# dronev2.net
KiCad netlist of a schematic drawn in Altium Designer
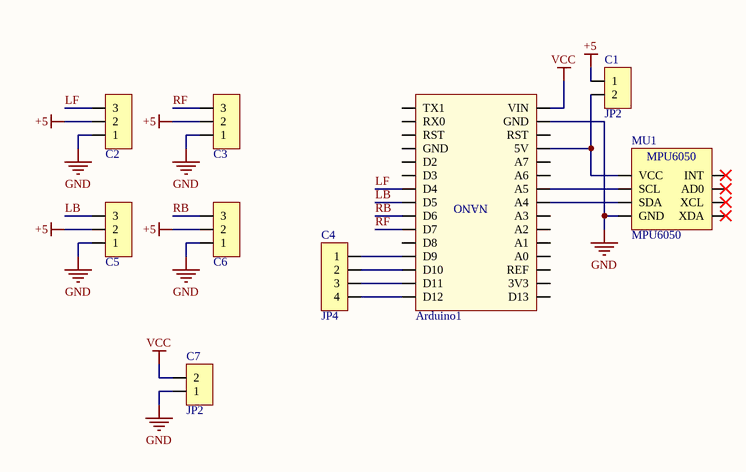
[diagram p0: dronev2.SchDoc]

(export (version "E")
  (design (tool "Eeschema 10.0.6"))
  (components
    (comp (ref "Arduino1")
      (value "Arduino Nano")
      (footprint "Arduino Nano")
      (description "Arduino NANO")
      (libsource (lib "LIBRARY") (part "Arduino Nano"))
    )
    (comp (ref "C1")
      (value "JP2")
      (footprint "JP2-CLOSED")
      (description "WR-PHD 2.54 mm Angled Socket Header")
      (fields
        (field (name "MANUFACTURER") "Würth Elektronik eiSos GmbH")
        (field (name "PARTNO") "613002143121")
        (field (name "CREATED BY") "Karrer Zheng")
      )
      (libsource (lib "") (part "JP2_1"))
    )
    (comp (ref "C2")
      (value "JP3")
      (footprint "JP3-C1T")
      (description "WR-PHD 2.54 mm Angled Socket Header")
      (fields
        (field (name "MANUFACTURER") "Würth Elektronik eiSos GmbH")
        (field (name "PARTNO") "613003143121")
        (field (name "CREATED BY") "Karrer Zheng")
      )
      (libsource (lib "LIBRARY") (part "JP3"))
    )
    (comp (ref "C3")
      (value "JP3")
      (footprint "JP3-C1T")
      (description "WR-PHD 2.54 mm Angled Socket Header")
      (fields
        (field (name "MANUFACTURER") "Würth Elektronik eiSos GmbH")
        (field (name "PARTNO") "613003143121")
        (field (name "CREATED BY") "Karrer Zheng")
      )
      (libsource (lib "LIBRARY") (part "JP3"))
    )
    (comp (ref "C4")
      (value "JP4")
      (footprint "JP4-C1T")
      (description "WR-PHD 2.54 mm Angled Socket Header")
      (fields
        (field (name "MANUFACTURER") "Würth Elektronik eiSos GmbH")
        (field (name "PARTNO") "613004143121")
        (field (name "CREATED BY") "Karrer Zheng")
      )
      (libsource (lib "LIBRARY") (part "JP4"))
    )
    (comp (ref "C5")
      (value "JP3")
      (footprint "JP3-C1T")
      (description "WR-PHD 2.54 mm Angled Socket Header")
      (fields
        (field (name "MANUFACTURER") "Würth Elektronik eiSos GmbH")
        (field (name "PARTNO") "613003143121")
        (field (name "CREATED BY") "Karrer Zheng")
      )
      (libsource (lib "LIBRARY") (part "JP3"))
    )
    (comp (ref "C6")
      (value "JP3")
      (footprint "JP3-C1T")
      (description "WR-PHD 2.54 mm Angled Socket Header")
      (fields
        (field (name "MANUFACTURER") "Würth Elektronik eiSos GmbH")
        (field (name "PARTNO") "613003143121")
        (field (name "CREATED BY") "Karrer Zheng")
      )
      (libsource (lib "LIBRARY") (part "JP3"))
    )
    (comp (ref "C7")
      (value "JP2")
      (footprint "JP2-C1T")
      (description "WR-PHD 2.54 mm Angled Socket Header")
      (fields
        (field (name "MANUFACTURER") "Würth Elektronik eiSos GmbH")
        (field (name "PARTNO") "613002143121")
        (field (name "CREATED BY") "Karrer Zheng")
      )
      (libsource (lib "LIBRARY") (part "JP2"))
    )
    (comp (ref "MU1")
      (value "MPU6050")
      (footprint "MPU6050")
      (fields
        (field (name "MANUFACTURER") "Würth Elektronik eiSos GmbH")
        (field (name "PARTNO") "613004143121")
        (field (name "CREATED BY") "Karrer Zheng")
      )
      (libsource (lib "LIBRARY") (part "MPU6050"))
    )
  )
  (nets
    (net (code "1") (name "+5") (class "Default")
      (node (ref "C1") (pin "1") (pinfunction "1_1") (pintype "passive"))
      (node (ref "C2") (pin "2") (pinfunction "2_2") (pintype "passive"))
      (node (ref "C3") (pin "2") (pinfunction "2_2") (pintype "passive"))
      (node (ref "C5") (pin "2") (pinfunction "2_2") (pintype "passive"))
      (node (ref "C6") (pin "2") (pinfunction "2_2") (pintype "passive"))
    )
    (net (code "2") (name "/LB") (class "Default")
      (node (ref "Arduino1") (pin "D5") (pinfunction "D5_D5") (pintype "passive"))
      (node (ref "C5") (pin "3") (pinfunction "3_3") (pintype "passive"))
    )
    (net (code "3") (name "/LF") (class "Default")
      (node (ref "Arduino1") (pin "D4") (pinfunction "D4_D4") (pintype "passive"))
      (node (ref "C2") (pin "3") (pinfunction "3_3") (pintype "passive"))
    )
    (net (code "4") (name "/RB") (class "Default")
      (node (ref "Arduino1") (pin "D6") (pinfunction "D6_D6") (pintype "passive"))
      (node (ref "C6") (pin "3") (pinfunction "3_3") (pintype "passive"))
    )
    (net (code "5") (name "/RF") (class "Default")
      (node (ref "Arduino1") (pin "D7") (pinfunction "D7_D7") (pintype "passive"))
      (node (ref "C3") (pin "3") (pinfunction "3_3") (pintype "passive"))
    )
    (net (code "6") (name "GND") (class "Default")
      (node (ref "Arduino1") (pin "GND") (pinfunction "GND_GND") (pintype "passive"))
      (node (ref "C2") (pin "1") (pinfunction "1_1") (pintype "passive"))
      (node (ref "C3") (pin "1") (pinfunction "1_1") (pintype "passive"))
      (node (ref "C5") (pin "1") (pinfunction "1_1") (pintype "passive"))
      (node (ref "C6") (pin "1") (pinfunction "1_1") (pintype "passive"))
      (node (ref "C7") (pin "1") (pinfunction "1_1") (pintype "passive"))
      (node (ref "MU1") (pin "2") (pinfunction "GND_2") (pintype "passive"))
    )
    (net (code "7") (name "Net-(Arduino1-PadD9)") (class "Default")
      (node (ref "Arduino1") (pin "D9") (pinfunction "D9_D9") (pintype "passive"))
      (node (ref "C4") (pin "1") (pinfunction "1_1") (pintype "passive"))
    )
    (net (code "8") (name "Net-(Arduino1-PadD10)") (class "Default")
      (node (ref "Arduino1") (pin "D10") (pinfunction "D10_D10") (pintype "passive"))
      (node (ref "C4") (pin "2") (pinfunction "2_2") (pintype "passive"))
    )
    (net (code "9") (name "Net-(Arduino1-PadD11)") (class "Default")
      (node (ref "Arduino1") (pin "D11") (pinfunction "D11_D11") (pintype "passive"))
      (node (ref "C4") (pin "3") (pinfunction "3_3") (pintype "passive"))
    )
    (net (code "10") (name "Net-(Arduino1-PadD12)") (class "Default")
      (node (ref "Arduino1") (pin "D12") (pinfunction "D12_D12") (pintype "passive"))
      (node (ref "C4") (pin "4") (pinfunction "4_4") (pintype "passive"))
    )
    (net (code "11") (name "Net-(MU1-SCL)") (class "Default")
      (node (ref "Arduino1") (pin "A5") (pinfunction "A5_A5") (pintype "passive"))
      (node (ref "MU1") (pin "3") (pinfunction "SCL_3") (pintype "passive"))
    )
    (net (code "12") (name "Net-(MU1-SDA)") (class "Default")
      (node (ref "Arduino1") (pin "A4") (pinfunction "A4_A4") (pintype "passive"))
      (node (ref "MU1") (pin "4") (pinfunction "SDA_4") (pintype "passive"))
    )
    (net (code "13") (name "Net-(MU1-VCC)") (class "Default")
      (node (ref "Arduino1") (pin "5V") (pinfunction "5V_5V") (pintype "passive"))
      (node (ref "C1") (pin "2") (pinfunction "2_2") (pintype "passive"))
      (node (ref "MU1") (pin "1") (pinfunction "VCC_1") (pintype "passive"))
    )
    (net (code "14") (name "VCC") (class "Default")
      (node (ref "Arduino1") (pin "VIN") (pinfunction "VIN_VIN") (pintype "passive"))
      (node (ref "C7") (pin "2") (pinfunction "2_2") (pintype "passive"))
    )
    (net (code "15") (name "unconnected-(Arduino1-Pad3V3)") (class "Default")
      (node (ref "Arduino1") (pin "3V3") (pinfunction "3V3_3V3") (pintype "passive"))
    )
    (net (code "16") (name "unconnected-(Arduino1-PadA0)") (class "Default")
      (node (ref "Arduino1") (pin "A0") (pinfunction "A0_A0") (pintype "passive"))
    )
    (net (code "17") (name "unconnected-(Arduino1-PadA1)") (class "Default")
      (node (ref "Arduino1") (pin "A1") (pinfunction "A1_A1") (pintype "passive"))
    )
    (net (code "18") (name "unconnected-(Arduino1-PadA2)") (class "Default")
      (node (ref "Arduino1") (pin "A2") (pinfunction "A2_A2") (pintype "passive"))
    )
    (net (code "19") (name "unconnected-(Arduino1-PadA3)") (class "Default")
      (node (ref "Arduino1") (pin "A3") (pinfunction "A3_A3") (pintype "passive"))
    )
    (net (code "20") (name "unconnected-(Arduino1-PadA6)") (class "Default")
      (node (ref "Arduino1") (pin "A6") (pinfunction "A6_A6") (pintype "passive"))
    )
    (net (code "21") (name "unconnected-(Arduino1-PadA7)") (class "Default")
      (node (ref "Arduino1") (pin "A7") (pinfunction "A7_A7") (pintype "passive"))
    )
    (net (code "22") (name "unconnected-(Arduino1-PadD2)") (class "Default")
      (node (ref "Arduino1") (pin "D2") (pinfunction "D2_D2") (pintype "passive"))
    )
    (net (code "23") (name "unconnected-(Arduino1-PadD3)") (class "Default")
      (node (ref "Arduino1") (pin "D3") (pinfunction "D3_D3") (pintype "passive"))
    )
    (net (code "24") (name "unconnected-(Arduino1-PadD8)") (class "Default")
      (node (ref "Arduino1") (pin "D8") (pinfunction "D8_D8") (pintype "passive"))
    )
    (net (code "25") (name "unconnected-(Arduino1-PadD13)") (class "Default")
      (node (ref "Arduino1") (pin "D13") (pinfunction "D13_D13") (pintype "passive"))
    )
    (net (code "26") (name "unconnected-(Arduino1-PadGND)") (class "Default")
      (node (ref "Arduino1") (pin "GND") (pinfunction "GND_GND") (pintype "passive"))
    )
    (net (code "27") (name "unconnected-(Arduino1-PadREF)") (class "Default")
      (node (ref "Arduino1") (pin "REF") (pinfunction "REF_REF") (pintype "passive"))
    )
    (net (code "28") (name "unconnected-(Arduino1-PadRST)") (class "Default")
      (node (ref "Arduino1") (pin "RST") (pinfunction "RST_RST") (pintype "passive"))
    )
    (net (code "29") (name "unconnected-(Arduino1-PadRST)_1") (class "Default")
      (node (ref "Arduino1") (pin "RST") (pinfunction "RST_RST") (pintype "passive"))
    )
    (net (code "30") (name "unconnected-(Arduino1-PadRX0)") (class "Default")
      (node (ref "Arduino1") (pin "RX0") (pinfunction "RX0_RX0") (pintype "passive"))
    )
    (net (code "31") (name "unconnected-(Arduino1-PadTX1)") (class "Default")
      (node (ref "Arduino1") (pin "TX1") (pinfunction "TX1_TX1") (pintype "passive"))
    )
    (net (code "32") (name "unconnected-(MU1-AD0-Pad7)") (class "Default")
      (node (ref "MU1") (pin "7") (pinfunction "AD0_7") (pintype "passive+no_connect"))
    )
    (net (code "33") (name "unconnected-(MU1-INT-Pad8)") (class "Default")
      (node (ref "MU1") (pin "8") (pinfunction "INT_8") (pintype "passive+no_connect"))
    )
    (net (code "34") (name "unconnected-(MU1-XCL-Pad6)") (class "Default")
      (node (ref "MU1") (pin "6") (pinfunction "XCL_6") (pintype "passive+no_connect"))
    )
    (net (code "35") (name "unconnected-(MU1-XDA-Pad5)") (class "Default")
      (node (ref "MU1") (pin "5") (pinfunction "XDA_5") (pintype "passive+no_connect"))
    )
  )
)
